# CAN_TERM_RIGHT.net
KiCad netlist of a schematic drawn in Altium Designer
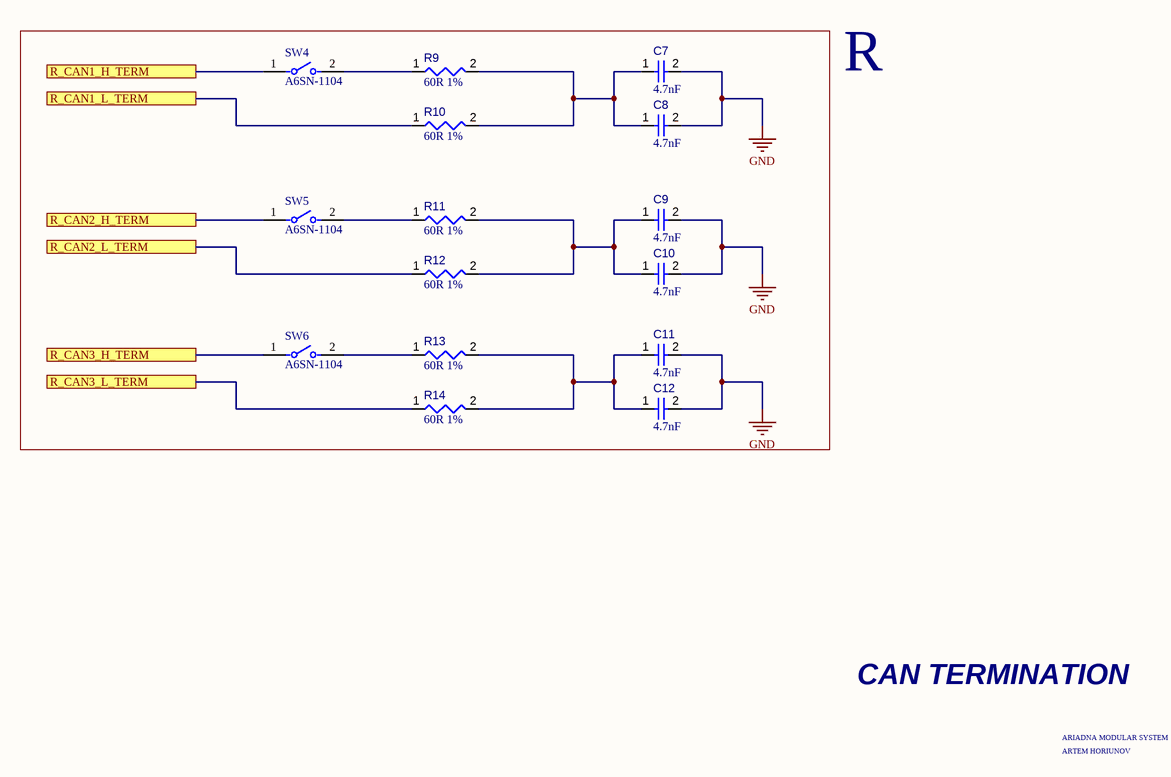
[diagram p0: CAN_TERM_RIGHT.SchDoc]

(export (version "E")
  (design (tool "Eeschema 10.0.6"))
  (components
    (comp (ref "C7")
      (value "4.7nF")
      (footprint "CAPC0805(2012)145_L")
      (description "Chip Capacitor, 4.7µF +/-40%, 25V, 0805, Thickness 1.45 mm")
      (fields (field (name "TOLERANCE") "20%") (field (name "Comment") "Capacitor 4.7µF +/-40% 25V 0805"))
      (libsource (lib "WUST") (part "CAP-NP-2"))
    )
    (comp (ref "C8")
      (value "4.7nF")
      (footprint "CAPC0805(2012)145_L")
      (description "Chip Capacitor, 4.7µF +/-40%, 25V, 0805, Thickness 1.45 mm")
      (fields (field (name "TOLERANCE") "20%") (field (name "Comment") "Capacitor 4.7µF +/-40% 25V 0805"))
      (libsource (lib "WUST") (part "CAP-NP-2"))
    )
    (comp (ref "C9")
      (value "4.7nF")
      (footprint "CAPC0805(2012)145_L")
      (description "Chip Capacitor, 4.7µF +/-40%, 25V, 0805, Thickness 1.45 mm")
      (fields (field (name "TOLERANCE") "20%") (field (name "Comment") "Capacitor 4.7µF +/-40% 25V 0805"))
      (libsource (lib "WUST") (part "CAP-NP-2"))
    )
    (comp (ref "C10")
      (value "4.7nF")
      (footprint "CAPC0805(2012)145_L")
      (description "Chip Capacitor, 4.7µF +/-40%, 25V, 0805, Thickness 1.45 mm")
      (fields (field (name "TOLERANCE") "20%") (field (name "Comment") "Capacitor 4.7µF +/-40% 25V 0805"))
      (libsource (lib "WUST") (part "CAP-NP-2"))
    )
    (comp (ref "C11")
      (value "4.7nF")
      (footprint "CAPC0805(2012)145_L")
      (description "Chip Capacitor, 4.7µF +/-40%, 25V, 0805, Thickness 1.45 mm")
      (fields (field (name "TOLERANCE") "20%") (field (name "Comment") "Capacitor 4.7µF +/-40% 25V 0805"))
      (libsource (lib "WUST") (part "CAP-NP-2"))
    )
    (comp (ref "C12")
      (value "4.7nF")
      (footprint "CAPC0805(2012)145_L")
      (description "Chip Capacitor, 4.7µF +/-40%, 25V, 0805, Thickness 1.45 mm")
      (fields (field (name "TOLERANCE") "20%") (field (name "Comment") "Capacitor 4.7µF +/-40% 25V 0805"))
      (libsource (lib "WUST") (part "CAP-NP-2"))
    )
    (comp (ref "R9")
      (value "60R 1%")
      (footprint "RESC0805(2012)_L")
      (description "4R7 0.125W 5% 0805 (2012 Metric)  SMD")
      (fields (field (name "POWER") "125mW") (field (name "TOLERANCE") "5%"))
      (libsource (lib "WUST") (part "4D7R5J"))
    )
    (comp (ref "R10")
      (value "60R 1%")
      (footprint "RESC0805(2012)_L")
      (description "4R7 0.125W 5% 0805 (2012 Metric)  SMD")
      (fields (field (name "POWER") "125mW") (field (name "TOLERANCE") "5%"))
      (libsource (lib "WUST") (part "4D7R5J"))
    )
    (comp (ref "R11")
      (value "60R 1%")
      (footprint "RESC0805(2012)_L")
      (description "4R7 0.125W 5% 0805 (2012 Metric)  SMD")
      (fields (field (name "POWER") "125mW") (field (name "TOLERANCE") "5%"))
      (libsource (lib "WUST") (part "4D7R5J"))
    )
    (comp (ref "R12")
      (value "60R 1%")
      (footprint "RESC0805(2012)_L")
      (description "4R7 0.125W 5% 0805 (2012 Metric)  SMD")
      (fields (field (name "POWER") "125mW") (field (name "TOLERANCE") "5%"))
      (libsource (lib "WUST") (part "4D7R5J"))
    )
    (comp (ref "R13")
      (value "60R 1%")
      (footprint "RESC0805(2012)_L")
      (description "4R7 0.125W 5% 0805 (2012 Metric)  SMD")
      (fields (field (name "POWER") "125mW") (field (name "TOLERANCE") "5%"))
      (libsource (lib "WUST") (part "4D7R5J"))
    )
    (comp (ref "R14")
      (value "60R 1%")
      (footprint "RESC0805(2012)_L")
      (description "4R7 0.125W 5% 0805 (2012 Metric)  SMD")
      (fields (field (name "POWER") "125mW") (field (name "TOLERANCE") "5%"))
      (libsource (lib "WUST") (part "4D7R5J"))
    )
    (comp (ref "SW4")
      (value "A6SN-1104")
      (footprint "FP-A6SN-1104-MFG")
      (description "SWITCH SLIDE DIP SPST 25MA 24V")
      (libsource (lib "Altium Content Vault") (part "bb27bde45df87f1f469753f287ef5ae"))
    )
    (comp (ref "SW5")
      (value "A6SN-1104")
      (footprint "FP-A6SN-1104-MFG")
      (description "SWITCH SLIDE DIP SPST 25MA 24V")
      (libsource (lib "Altium Content Vault") (part "bb27bde45df87f1f469753f287ef5ae"))
    )
    (comp (ref "SW6")
      (value "A6SN-1104")
      (footprint "FP-A6SN-1104-MFG")
      (description "SWITCH SLIDE DIP SPST 25MA 24V")
      (libsource (lib "Altium Content Vault") (part "bb27bde45df87f1f469753f287ef5ae"))
    )
  )
  (nets
    (net (code "1") (name "/R_CAN1_H_TERM") (class "Default")
      (node (ref "SW4") (pin "1") (pinfunction "1_1") (pintype "passive"))
    )
    (net (code "2") (name "/R_CAN1_L_TERM") (class "Default")
      (node (ref "R10") (pin "1") (pinfunction "1_1") (pintype "passive"))
    )
    (net (code "3") (name "/R_CAN2_H_TERM") (class "Default")
      (node (ref "SW5") (pin "1") (pinfunction "1_1") (pintype "passive"))
    )
    (net (code "4") (name "/R_CAN2_L_TERM") (class "Default")
      (node (ref "R12") (pin "1") (pinfunction "1_1") (pintype "passive"))
    )
    (net (code "5") (name "/R_CAN3_H_TERM") (class "Default")
      (node (ref "SW6") (pin "1") (pinfunction "1_1") (pintype "passive"))
    )
    (net (code "6") (name "/R_CAN3_L_TERM") (class "Default")
      (node (ref "R14") (pin "1") (pinfunction "1_1") (pintype "passive"))
    )
    (net (code "7") (name "GND") (class "Default")
      (node (ref "C10") (pin "2") (pinfunction "2_2") (pintype "passive"))
      (node (ref "C11") (pin "2") (pinfunction "2_2") (pintype "passive"))
      (node (ref "C12") (pin "2") (pinfunction "2_2") (pintype "passive"))
      (node (ref "C7") (pin "2") (pinfunction "2_2") (pintype "passive"))
      (node (ref "C8") (pin "2") (pinfunction "2_2") (pintype "passive"))
      (node (ref "C9") (pin "2") (pinfunction "2_2") (pintype "passive"))
    )
    (net (code "8") (name "Net-(C7-Pad1)") (class "Default")
      (node (ref "C7") (pin "1") (pinfunction "1_1") (pintype "passive"))
      (node (ref "C8") (pin "1") (pinfunction "1_1") (pintype "passive"))
      (node (ref "R10") (pin "2") (pinfunction "2_2") (pintype "passive"))
      (node (ref "R9") (pin "2") (pinfunction "2_2") (pintype "passive"))
    )
    (net (code "9") (name "Net-(C10-Pad1)") (class "Default")
      (node (ref "C10") (pin "1") (pinfunction "1_1") (pintype "passive"))
      (node (ref "C9") (pin "1") (pinfunction "1_1") (pintype "passive"))
      (node (ref "R11") (pin "2") (pinfunction "2_2") (pintype "passive"))
      (node (ref "R12") (pin "2") (pinfunction "2_2") (pintype "passive"))
    )
    (net (code "10") (name "Net-(C11-Pad1)") (class "Default")
      (node (ref "C11") (pin "1") (pinfunction "1_1") (pintype "passive"))
      (node (ref "C12") (pin "1") (pinfunction "1_1") (pintype "passive"))
      (node (ref "R13") (pin "2") (pinfunction "2_2") (pintype "passive"))
      (node (ref "R14") (pin "2") (pinfunction "2_2") (pintype "passive"))
    )
    (net (code "11") (name "Net-(R9-Pad1)") (class "Default")
      (node (ref "R9") (pin "1") (pinfunction "1_1") (pintype "passive"))
      (node (ref "SW4") (pin "2") (pinfunction "2_2") (pintype "passive"))
    )
    (net (code "12") (name "Net-(R11-Pad1)") (class "Default")
      (node (ref "R11") (pin "1") (pinfunction "1_1") (pintype "passive"))
      (node (ref "SW5") (pin "2") (pinfunction "2_2") (pintype "passive"))
    )
    (net (code "13") (name "Net-(R13-Pad1)") (class "Default")
      (node (ref "R13") (pin "1") (pinfunction "1_1") (pintype "passive"))
      (node (ref "SW6") (pin "2") (pinfunction "2_2") (pintype "passive"))
    )
  )
)
